# Ref_4V096_LM4132AMF.net
KiCad netlist of a schematic drawn in Altium Designer
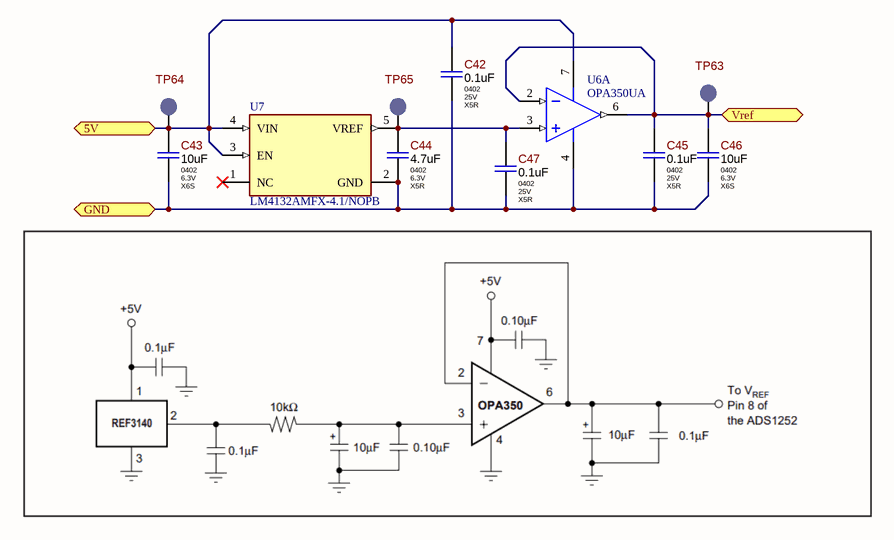
[diagram p0: Ref_4V096_LM4132AMF.SchDoc]

(export (version "E")
  (design (tool "Eeschema 10.0.6"))
  (components
    (comp (ref "C42")
      (value "0.1uF")
      (footprint "C_CERAMIC_0402_MED")
      (description "100nF 25V X5R ±10% 0402 Ceramic Capacitor RoHS")
      (fields
        (field (name "PACKAGE") "0402")
        (field (name "VOLTAGE") "25V")
        (field (name "DIELECTRIC TYPE") "X5R")
        (field (name "PART NUMBER") "CL05A104KA5NNNC")
        (field (name "MANUFACTURER") "Samsung Electro-Mechanics")
      )
      (libsource (lib "EL.XXX.T01") (part "Capacitor-NonPolar"))
    )
    (comp (ref "C43")
      (value "10uF")
      (footprint "C_CERAMIC_0402_MED")
      (description "10uF 6.3V X6S ±20% 0402 Ceramic Capacitor RoHS")
      (fields
        (field (name "PACKAGE") "0402")
        (field (name "VOLTAGE") "6.3V")
        (field (name "DIELECTRIC TYPE") "X6S")
        (field (name "PART NUMBER") "GRM155C80J106ME11D")
        (field (name "MANUFACTURER") "Murata Electronics")
      )
      (libsource (lib "EL.XXX.T01") (part "Capacitor-NonPolar"))
    )
    (comp (ref "C44")
      (value "4.7uF")
      (footprint "C_CERAMIC_0402_MED")
      (description "4.7uF 6.3V X5R ±20% 0402 Ceramic Capacitor RoHS")
      (fields
        (field (name "PACKAGE") "0402")
        (field (name "VOLTAGE") "6.3V")
        (field (name "DIELECTRIC TYPE") "X5R")
        (field (name "PART NUMBER") "GRM155R60J475ME47")
        (field (name "MANUFACTURER") "Murata Electronics")
      )
      (libsource (lib "EL.XXX.T01") (part "Capacitor-NonPolar"))
    )
    (comp (ref "C45")
      (value "0.1uF")
      (footprint "C_CERAMIC_0402_MED")
      (description "100nF 25V X5R ±10% 0402 Ceramic Capacitor RoHS")
      (fields
        (field (name "PACKAGE") "0402")
        (field (name "VOLTAGE") "25V")
        (field (name "DIELECTRIC TYPE") "X5R")
        (field (name "PART NUMBER") "CL05A104KA5NNNC")
        (field (name "MANUFACTURER") "Samsung Electro-Mechanics")
      )
      (libsource (lib "EL.XXX.T01") (part "Capacitor-NonPolar"))
    )
    (comp (ref "C46")
      (value "10uF")
      (footprint "C_CERAMIC_0402_MED")
      (description "10uF 6.3V X6S ±20% 0402 Ceramic Capacitor RoHS")
      (fields
        (field (name "PACKAGE") "0402")
        (field (name "VOLTAGE") "6.3V")
        (field (name "DIELECTRIC TYPE") "X6S")
        (field (name "PART NUMBER") "GRM155C80J106ME11D")
        (field (name "MANUFACTURER") "Murata Electronics")
      )
      (libsource (lib "EL.XXX.T01") (part "Capacitor-NonPolar"))
    )
    (comp (ref "C47")
      (value "0.1uF")
      (footprint "C_CERAMIC_0402_MED")
      (description "100nF 25V X5R ±10% 0402 Ceramic Capacitor RoHS")
      (fields
        (field (name "PACKAGE") "0402")
        (field (name "VOLTAGE") "25V")
        (field (name "DIELECTRIC TYPE") "X5R")
        (field (name "PART NUMBER") "CL05A104KA5NNNC")
        (field (name "MANUFACTURER") "Samsung Electro-Mechanics")
      )
      (libsource (lib "EL.XXX.T01") (part "Capacitor-NonPolar"))
    )
    (comp (ref "TP63")
      (value "LED_LINK")
      (footprint "TP_SMD_2mm")
      (description "Test Point SMD Pad 1.0mm/1.5mm/2mm")
      (fields (field (name "PART NUMBER") "TP-PAD-SMD"))
      (libsource (lib "EL.XXX.T01") (part "Test-Point-SMD-1"))
    )
    (comp (ref "TP64")
      (value "LED_LINK")
      (footprint "TP_SMD_2mm")
      (description "Test Point SMD Pad 1.0mm/1.5mm/2mm")
      (fields (field (name "PART NUMBER") "TP-PAD-SMD"))
      (libsource (lib "EL.XXX.T01") (part "Test-Point-SMD-1"))
    )
    (comp (ref "TP65")
      (value "LED_LINK")
      (footprint "TP_SMD_2mm")
      (description "Test Point SMD Pad 1.0mm/1.5mm/2mm")
      (fields (field (name "PART NUMBER") "TP-PAD-SMD"))
      (libsource (lib "EL.XXX.T01") (part "Test-Point-SMD-1"))
    )
    (comp (ref "U6")
      (value "OPA350UA")
      (footprint "D0008A_M")
      (fields (field (name "MANUFACTURER") "Texas Instruments"))
      (libsource (lib "EL.XXX.T01") (part "TI-OPA-8_1"))
    )
    (comp (ref "U7")
      (value "LM4132AMFX-4.1/NOPB")
      (footprint "SOT-23-5")
      (description "IC VREF SERIES 0.05% SOT23-5")
      (fields (field (name "TOLERANCE") "0.05%"))
      (libsource (lib "EL.XXX.T01") (part "LM4132AMFX-4.1/NOPB"))
    )
  )
  (nets
    (net (code "1") (name "/5V") (class "Default")
      (node (ref "C42") (pin "1") (pinfunction "1_1") (pintype "passive"))
      (node (ref "C43") (pin "1") (pinfunction "1_1") (pintype "passive"))
      (node (ref "TP64") (pin "1") (pintype "passive"))
      (node (ref "U6") (pin "7") (pinfunction "V+_7") (pintype "power_in"))
      (node (ref "U7") (pin "3") (pinfunction "EN_3") (pintype "input"))
      (node (ref "U7") (pin "4") (pinfunction "VIN_4") (pintype "input"))
    )
    (net (code "2") (name "/GND") (class "Default")
      (node (ref "C42") (pin "2") (pinfunction "2_2") (pintype "passive"))
      (node (ref "C43") (pin "2") (pinfunction "2_2") (pintype "passive"))
      (node (ref "C44") (pin "2") (pinfunction "2_2") (pintype "passive"))
      (node (ref "C45") (pin "2") (pinfunction "2_2") (pintype "passive"))
      (node (ref "C46") (pin "2") (pinfunction "2_2") (pintype "passive"))
      (node (ref "C47") (pin "2") (pinfunction "2_2") (pintype "passive"))
      (node (ref "U6") (pin "4") (pinfunction "V-_4") (pintype "power_in"))
      (node (ref "U7") (pin "2") (pinfunction "GND_2") (pintype "power_in"))
    )
    (net (code "3") (name "/Vref") (class "Default")
      (node (ref "C45") (pin "1") (pinfunction "1_1") (pintype "passive"))
      (node (ref "C46") (pin "1") (pinfunction "1_1") (pintype "passive"))
      (node (ref "TP63") (pin "1") (pintype "passive"))
      (node (ref "U6") (pin "2") (pinfunction "IN-_2") (pintype "input"))
      (node (ref "U6") (pin "6") (pinfunction "OUT_6") (pintype "output"))
    )
    (net (code "4") (name "Net-(U6A-IN+)") (class "Default")
      (node (ref "C44") (pin "1") (pinfunction "1_1") (pintype "passive"))
      (node (ref "C47") (pin "1") (pinfunction "1_1") (pintype "passive"))
      (node (ref "TP65") (pin "1") (pintype "passive"))
      (node (ref "U6") (pin "3") (pinfunction "IN+_3") (pintype "input"))
      (node (ref "U7") (pin "5") (pinfunction "VREF_5") (pintype "output"))
    )
    (net (code "5") (name "unconnected-(U7-NC-Pad1)") (class "Default")
      (node (ref "U7") (pin "1") (pinfunction "NC_1") (pintype "passive+no_connect"))
    )
  )
)
